# CT.net
KiCad netlist of a schematic drawn in EasyEDA Pro
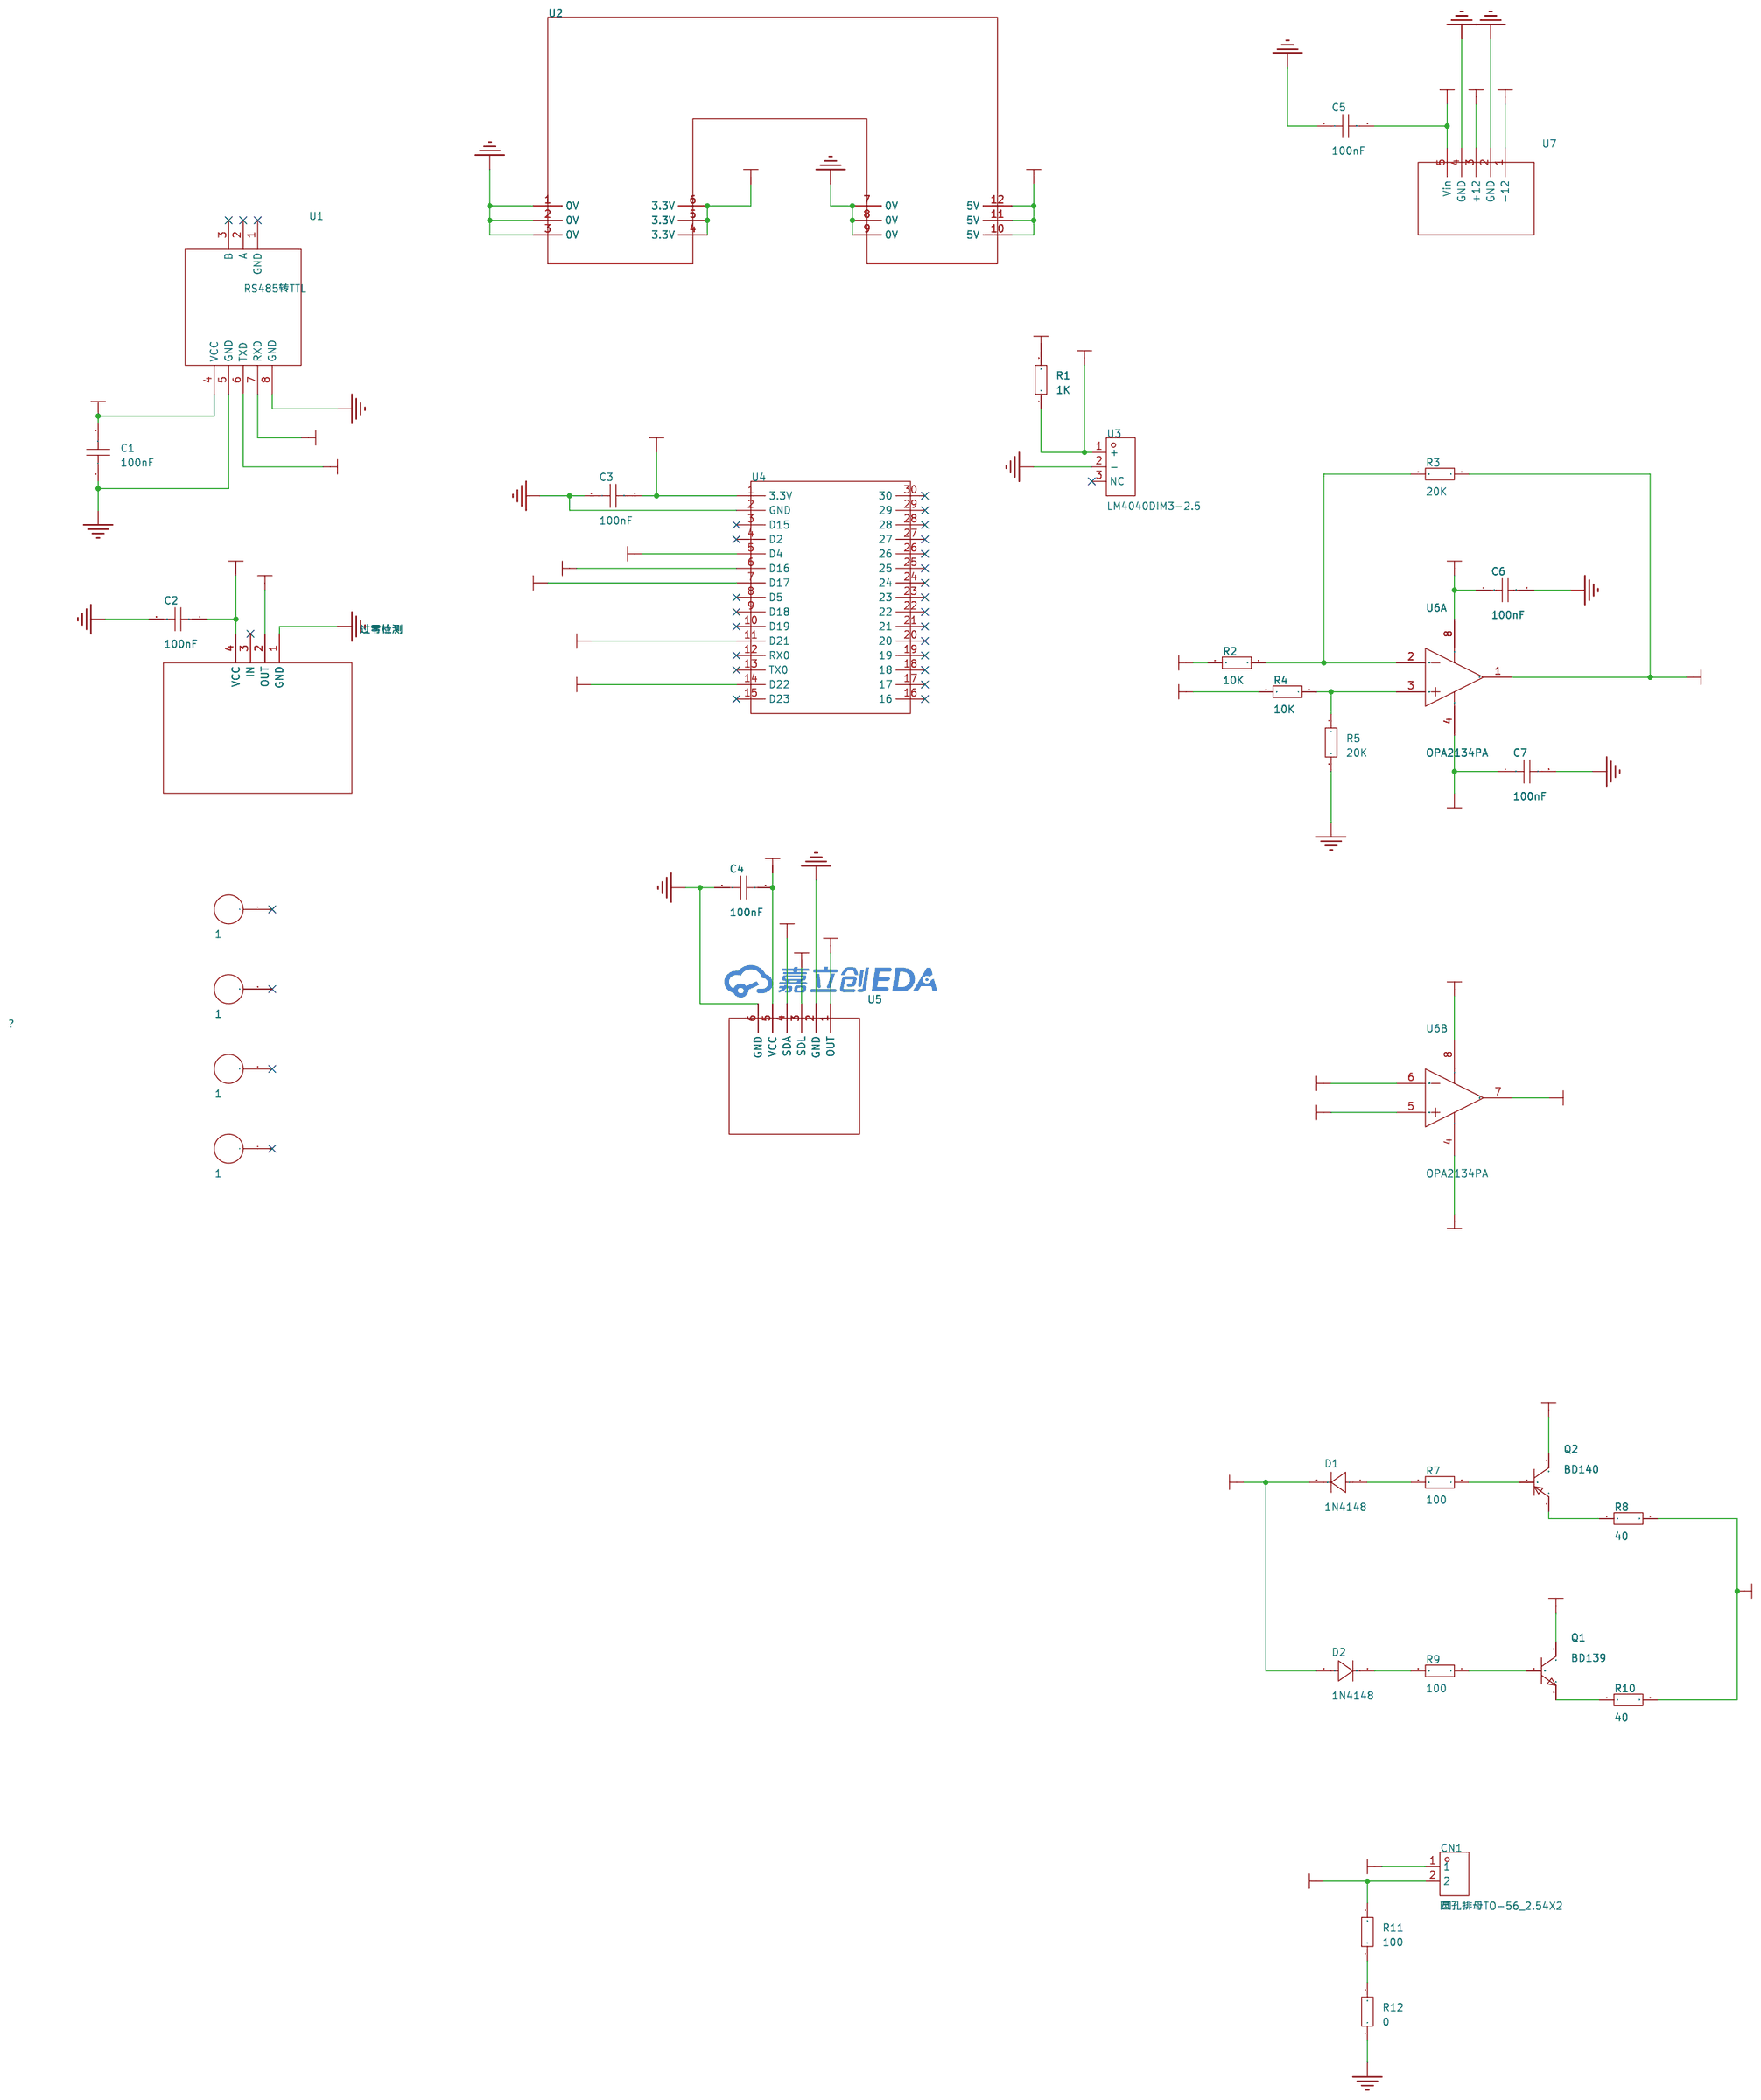
[diagram p0: schematic sheet]

(export (version "E")
  (design (tool "Eeschema 10.0.6"))
  (components
    (comp (ref "C1")
      (value "100nF")
      (footprint "easyedapro:C0805")
      (description "容值:100uF;精度:±20%;额定电压:4V;温度系数:X6S;")
      (fields
        (field (name "Manufacturer Part") "CGA0805X6S107M4R0MT")
        (field (name "Manufacturer") "HRE(芯声)")
      )
      (libsource (lib "easyedapro") (part "CGA0805X6S107M4R0MT"))
    )
    (comp (ref "C2")
      (value "100nF")
      (footprint "easyedapro:C0805")
      (description "容值:100uF;精度:±20%;额定电压:4V;温度系数:X6S;")
      (fields
        (field (name "Manufacturer Part") "CGA0805X6S107M4R0MT")
        (field (name "Manufacturer") "HRE(芯声)")
      )
      (libsource (lib "easyedapro") (part "CGA0805X6S107M4R0MT"))
    )
    (comp (ref "C3")
      (value "100nF")
      (footprint "easyedapro:C0805")
      (description "容值:100uF;精度:±20%;额定电压:4V;温度系数:X6S;")
      (fields
        (field (name "Manufacturer Part") "CGA0805X6S107M4R0MT")
        (field (name "Manufacturer") "HRE(芯声)")
      )
      (libsource (lib "easyedapro") (part "CGA0805X6S107M4R0MT"))
    )
    (comp (ref "C4")
      (value "100nF")
      (footprint "easyedapro:C0805")
      (description "容值:100uF;精度:±20%;额定电压:4V;温度系数:X6S;")
      (fields
        (field (name "Manufacturer Part") "CGA0805X6S107M4R0MT")
        (field (name "Manufacturer") "HRE(芯声)")
      )
      (libsource (lib "easyedapro") (part "CGA0805X6S107M4R0MT"))
    )
    (comp (ref "C5")
      (value "100nF")
      (footprint "easyedapro:C0805")
      (description "容值:100uF;精度:±20%;额定电压:4V;温度系数:X6S;")
      (fields
        (field (name "Manufacturer Part") "CGA0805X6S107M4R0MT")
        (field (name "Manufacturer") "HRE(芯声)")
      )
      (libsource (lib "easyedapro") (part "CGA0805X6S107M4R0MT"))
    )
    (comp (ref "C6")
      (value "100nF")
      (footprint "easyedapro:C0805")
      (description "容值:100uF;精度:±20%;额定电压:4V;温度系数:X6S;")
      (fields
        (field (name "Manufacturer Part") "CGA0805X6S107M4R0MT")
        (field (name "Manufacturer") "HRE(芯声)")
      )
      (libsource (lib "easyedapro") (part "CGA0805X6S107M4R0MT"))
    )
    (comp (ref "C7")
      (value "100nF")
      (footprint "easyedapro:C0805")
      (description "容值:100uF;精度:±20%;额定电压:4V;温度系数:X6S;")
      (fields
        (field (name "Manufacturer Part") "CGA0805X6S107M4R0MT")
        (field (name "Manufacturer") "HRE(芯声)")
      )
      (libsource (lib "easyedapro") (part "CGA0805X6S107M4R0MT"))
    )
    (comp (ref "CN1")
      (value "圆孔排母TO-56_2.54X2")
      (footprint "easyedapro:CONN-TH_TO-56_2.54-2")
      (libsource (lib "easyedapro") (part "圆孔排母TO-56_2.54X2"))
    )
    (comp (ref "D1")
      (value "1N4148")
      (footprint "easyedapro:DO-35_BD2.2-L4.0-D0.50_1N4148")
      (description "正向压降(Vf):1V@10mA;直流反向耐压(Vr):100V;整流电流:150mA;反向恢复时间(Trr):4ns;")
      (fields (field (name "Manufacturer") "LJ(朗捷)"))
      (libsource (lib "easyedapro") (part "1N4148_C18195411"))
    )
    (comp (ref "D2")
      (value "1N4148")
      (footprint "easyedapro:DO-35_BD2.2-L4.0-D0.50_1N4148")
      (description "正向压降(Vf):1V@10mA;直流反向耐压(Vr):100V;整流电流:150mA;反向恢复时间(Trr):4ns;")
      (fields (field (name "Manufacturer") "LJ(朗捷)"))
      (libsource (lib "easyedapro") (part "1N4148_C18195411"))
    )
    (comp (ref "Q1")
      (value "BD139")
      (footprint "easyedapro:TO-126_L7.5-W2.5-P2.3-B")
      (description "晶体管类型:NPN;集电极电流(Ic):1.5A;集射极击穿电压(Vceo):80V;耗散功率(Pd):12.5W;直流电流增益(hFE):63@150mA,2V;")
      (fields (field (name "Manufacturer") "ST(意法半导体)"))
      (libsource (lib "easyedapro") (part "BD139"))
    )
    (comp (ref "Q2")
      (value "BD140")
      (footprint "easyedapro:TO-126_L8.3-W3.5-P2.29-T")
      (description "晶体管类型:PNP;集电极电流(Ic):1.5A;集射极击穿电压(Vceo):80V;耗散功率(Pd):1.25W;直流电流增益(hFE):40@150mA,2V;")
      (fields (field (name "Manufacturer") "CJ(江苏长电/长晶)"))
      (libsource (lib "easyedapro") (part "BD140_C20604"))
    )
    (comp (ref "R1")
      (value "1K")
      (footprint "easyedapro:R0805")
      (description "电阻类型:厚膜电阻;阻值:1MΩ;精度:±1%;功率:125mW;最大工作电压:150V;温度系数:±100ppm/°C;")
      (fields
        (field (name "Manufacturer Part") "0805W8F1004T5E")
        (field (name "Manufacturer") "UNI-ROYAL(厚声)")
      )
      (libsource (lib "easyedapro") (part "0805W8F1004T5E"))
    )
    (comp (ref "R2")
      (value "10K")
      (footprint "easyedapro:R0805")
      (description "电阻类型:厚膜电阻;阻值:1MΩ;精度:±1%;功率:125mW;最大工作电压:150V;温度系数:±100ppm/°C;")
      (fields
        (field (name "Manufacturer Part") "0805W8F1004T5E")
        (field (name "Manufacturer") "UNI-ROYAL(厚声)")
      )
      (libsource (lib "easyedapro") (part "0805W8F1004T5E"))
    )
    (comp (ref "R3")
      (value "20K")
      (footprint "easyedapro:R0805")
      (description "电阻类型:厚膜电阻;阻值:1MΩ;精度:±1%;功率:125mW;最大工作电压:150V;温度系数:±100ppm/°C;")
      (fields
        (field (name "Manufacturer Part") "0805W8F1004T5E")
        (field (name "Manufacturer") "UNI-ROYAL(厚声)")
      )
      (libsource (lib "easyedapro") (part "0805W8F1004T5E"))
    )
    (comp (ref "R4")
      (value "10K")
      (footprint "easyedapro:R0805")
      (description "电阻类型:厚膜电阻;阻值:1MΩ;精度:±1%;功率:125mW;最大工作电压:150V;温度系数:±100ppm/°C;")
      (fields
        (field (name "Manufacturer Part") "0805W8F1004T5E")
        (field (name "Manufacturer") "UNI-ROYAL(厚声)")
      )
      (libsource (lib "easyedapro") (part "0805W8F1004T5E"))
    )
    (comp (ref "R5")
      (value "20K")
      (footprint "easyedapro:R0805")
      (description "电阻类型:厚膜电阻;阻值:1MΩ;精度:±1%;功率:125mW;最大工作电压:150V;温度系数:±100ppm/°C;")
      (fields
        (field (name "Manufacturer Part") "0805W8F1004T5E")
        (field (name "Manufacturer") "UNI-ROYAL(厚声)")
      )
      (libsource (lib "easyedapro") (part "0805W8F1004T5E"))
    )
    (comp (ref "R7")
      (value "100")
      (footprint "easyedapro:R0805")
      (description "电阻类型:厚膜电阻;阻值:1MΩ;精度:±1%;功率:125mW;最大工作电压:150V;温度系数:±100ppm/°C;")
      (fields
        (field (name "Manufacturer Part") "0805W8F1004T5E")
        (field (name "Manufacturer") "UNI-ROYAL(厚声)")
      )
      (libsource (lib "easyedapro") (part "0805W8F1004T5E"))
    )
    (comp (ref "R8")
      (value "40")
      (footprint "easyedapro:R0805")
      (description "电阻类型:厚膜电阻;阻值:1MΩ;精度:±1%;功率:125mW;最大工作电压:150V;温度系数:±100ppm/°C;")
      (fields
        (field (name "Manufacturer Part") "0805W8F1004T5E")
        (field (name "Manufacturer") "UNI-ROYAL(厚声)")
      )
      (libsource (lib "easyedapro") (part "0805W8F1004T5E"))
    )
    (comp (ref "R9")
      (value "100")
      (footprint "easyedapro:R0805")
      (description "电阻类型:厚膜电阻;阻值:1MΩ;精度:±1%;功率:125mW;最大工作电压:150V;温度系数:±100ppm/°C;")
      (fields
        (field (name "Manufacturer Part") "0805W8F1004T5E")
        (field (name "Manufacturer") "UNI-ROYAL(厚声)")
      )
      (libsource (lib "easyedapro") (part "0805W8F1004T5E"))
    )
    (comp (ref "R10")
      (value "40")
      (footprint "easyedapro:R0805")
      (description "电阻类型:厚膜电阻;阻值:1MΩ;精度:±1%;功率:125mW;最大工作电压:150V;温度系数:±100ppm/°C;")
      (fields
        (field (name "Manufacturer Part") "0805W8F1004T5E")
        (field (name "Manufacturer") "UNI-ROYAL(厚声)")
      )
      (libsource (lib "easyedapro") (part "0805W8F1004T5E"))
    )
    (comp (ref "R11")
      (value "100")
      (footprint "easyedapro:R0805")
      (description "电阻类型:厚膜电阻;阻值:1MΩ;精度:±1%;功率:125mW;最大工作电压:150V;温度系数:±100ppm/°C;")
      (fields
        (field (name "Manufacturer Part") "0805W8F1004T5E")
        (field (name "Manufacturer") "UNI-ROYAL(厚声)")
      )
      (libsource (lib "easyedapro") (part "0805W8F1004T5E"))
    )
    (comp (ref "R12")
      (value "0")
      (footprint "easyedapro:R0805")
      (description "电阻类型:厚膜电阻;阻值:1MΩ;精度:±1%;功率:125mW;最大工作电压:150V;温度系数:±100ppm/°C;")
      (fields
        (field (name "Manufacturer Part") "0805W8F1004T5E")
        (field (name "Manufacturer") "UNI-ROYAL(厚声)")
      )
      (libsource (lib "easyedapro") (part "0805W8F1004T5E"))
    )
    (comp (ref "U1")
      (value "RS485转TTL")
      (footprint "easyedapro:RS485转TTL")
      (libsource (lib "easyedapro") (part "元件"))
    )
    (comp (ref "U2")
      (value "~")
      (footprint "easyedapro:9V1A供电")
      (libsource (lib "easyedapro") (part "9V1A供电"))
    )
    (comp (ref "U3")
      (value "LM4040DIM3-2.5")
      (footprint "easyedapro:SOT-23-3_L2.9-W1.3-P1.90-LS2.4-BR")
      (description "输出类型:固定;输出电压:2.5V;输出电流:15mA;精度:±1%;")
      (fields (field (name "Manufacturer") "TI(德州仪器)"))
      (libsource (lib "easyedapro") (part "LM4040DIM3-2.5_C3717666"))
    )
    (comp (ref "U4") (value "~") (footprint "easyedapro:ESP32") (libsource (lib "easyedapro") (part "ESP32")))
    (comp (ref "U5")
      (value "~")
      (footprint "easyedapro:mcp4725")
      (libsource (lib "easyedapro") (part "mcp4725"))
    )
    (comp (ref "U6")
      (value "OPA2134PA")
      (footprint "easyedapro:DIP-8_L9.6-W6.4-P2.54-LS7.6-BL-1")
      (description "功放类型:-;扬声器通道数:双声道;输出功率:-;")
      (fields (field (name "Manufacturer") "TI(德州仪器)"))
      (libsource (lib "easyedapro") (part "OPA2134PA"))
    )
    (comp (ref "U7")
      (value "~")
      (footprint "easyedapro:12/-12")
      (libsource (lib "easyedapro") (part "12/-12"))
    )
    (comp (ref "V-PB2")
      (value "1")
      (footprint "easyedapro:SMD_BD4.2-L4.7-W4.7-D3.0")
      (description "M3*5+6")
      (fields (field (name "Manufacturer") "国产"))
      (libsource (lib "easyedapro") (part "铜柱M3*5+6"))
    )
    (comp (ref "V-PB3")
      (value "1")
      (footprint "easyedapro:SMD_BD4.2-L4.7-W4.7-D3.0")
      (description "M3*5+6")
      (fields (field (name "Manufacturer") "国产"))
      (libsource (lib "easyedapro") (part "铜柱M3*5+6"))
    )
    (comp (ref "V-PB4")
      (value "1")
      (footprint "easyedapro:SMD_BD4.2-L4.7-W4.7-D3.0")
      (description "M3*5+6")
      (fields (field (name "Manufacturer") "国产"))
      (libsource (lib "easyedapro") (part "铜柱M3*5+6"))
    )
    (comp (ref "V-PB5")
      (value "1")
      (footprint "easyedapro:SMD_BD4.2-L4.7-W4.7-D3.0")
      (description "M3*5+6")
      (fields (field (name "Manufacturer") "国产"))
      (libsource (lib "easyedapro") (part "铜柱M3*5+6"))
    )
    (comp (ref "过零检测") (value "~") (footprint "easyedapro:过零检测") (libsource (lib "easyedapro") (part "过零检测")))
  )
  (nets
    (net (code "1") (name "+12V") (class "Default")
      (node (ref "C6") (pin "1") (pinfunction "1_1") (pintype "unspecified"))
      (node (ref "Q1") (pin "2") (pinfunction "C_2") (pintype "unspecified"))
      (node (ref "U6") (pin "8") (pinfunction "V+_8") (pintype "unspecified"))
      (node (ref "U7") (pin "3") (pinfunction "+12_3") (pintype "input"))
    )
    (net (code "2") (name "-12V") (class "Default")
      (node (ref "C7") (pin "1") (pinfunction "1_1") (pintype "unspecified"))
      (node (ref "Q2") (pin "2") (pinfunction "C_2") (pintype "input"))
      (node (ref "U6") (pin "4") (pinfunction "V-_4") (pintype "unspecified"))
      (node (ref "U7") (pin "1") (pinfunction "-12_1") (pintype "input"))
    )
    (net (code "3") (name "3.3V") (class "Default")
      (node (ref "C1") (pin "2") (pinfunction "2_2") (pintype "unspecified"))
      (node (ref "C2") (pin "1") (pinfunction "1_1") (pintype "unspecified"))
      (node (ref "C3") (pin "2") (pinfunction "2_2") (pintype "unspecified"))
      (node (ref "U1") (pin "4") (pinfunction "VCC_4") (pintype "input"))
      (node (ref "U2") (pin "4") (pinfunction "3.3V_4") (pintype "input"))
      (node (ref "U2") (pin "5") (pinfunction "3.3V_5") (pintype "input"))
      (node (ref "U2") (pin "6") (pinfunction "3.3V_6") (pintype "input"))
      (node (ref "U4") (pin "1") (pinfunction "3.3V_1") (pintype "input"))
      (node (ref "过零检测") (pin "4") (pinfunction "VCC_4") (pintype "input"))
    )
    (net (code "4") (name "5V") (class "Default")
      (node (ref "C4") (pin "2") (pinfunction "2_2") (pintype "unspecified"))
      (node (ref "C5") (pin "2") (pinfunction "2_2") (pintype "unspecified"))
      (node (ref "R1") (pin "2") (pinfunction "2_2") (pintype "input"))
      (node (ref "U2") (pin "10") (pinfunction "5V_10") (pintype "input"))
      (node (ref "U2") (pin "11") (pinfunction "5V_11") (pintype "input"))
      (node (ref "U2") (pin "12") (pinfunction "5V_12") (pintype "input"))
      (node (ref "U5") (pin "5") (pinfunction "VCC_5") (pintype "input"))
      (node (ref "U7") (pin "5") (pinfunction "Vin_5") (pintype "input"))
    )
    (net (code "5") (name "CT+") (class "Default")
      (node (ref "CN1") (pin "1") (pinfunction "1_1") (pintype "unspecified"))
      (node (ref "R10") (pin "2") (pinfunction "2_2") (pintype "input"))
      (node (ref "R8") (pin "2") (pinfunction "2_2") (pintype "input"))
    )
    (net (code "6") (name "CT-") (class "Default")
      (node (ref "CN1") (pin "2") (pinfunction "2_2") (pintype "unspecified"))
      (node (ref "R11") (pin "2") (pinfunction "2_2") (pintype "input"))
      (node (ref "U6") (pin "6") (pinfunction "-IN_B_6") (pintype "unspecified"))
    )
    (net (code "7") (name "GND") (class "Default")
      (node (ref "C1") (pin "1") (pinfunction "1_1") (pintype "unspecified"))
      (node (ref "C2") (pin "2") (pinfunction "2_2") (pintype "unspecified"))
      (node (ref "C3") (pin "1") (pinfunction "1_1") (pintype "unspecified"))
      (node (ref "C4") (pin "1") (pinfunction "1_1") (pintype "unspecified"))
      (node (ref "C5") (pin "1") (pinfunction "1_1") (pintype "unspecified"))
      (node (ref "C6") (pin "2") (pinfunction "2_2") (pintype "unspecified"))
      (node (ref "C7") (pin "2") (pinfunction "2_2") (pintype "unspecified"))
      (node (ref "R12") (pin "1") (pinfunction "1_1") (pintype "input"))
      (node (ref "R5") (pin "2") (pinfunction "2_2") (pintype "input"))
      (node (ref "U1") (pin "5") (pinfunction "GND_5") (pintype "input"))
      (node (ref "U1") (pin "8") (pinfunction "GND_8") (pintype "input"))
      (node (ref "U2") (pin "1") (pinfunction "0V_1") (pintype "input"))
      (node (ref "U2") (pin "2") (pinfunction "0V_2") (pintype "input"))
      (node (ref "U2") (pin "3") (pinfunction "0V_3") (pintype "input"))
      (node (ref "U2") (pin "7") (pinfunction "0V_7") (pintype "input"))
      (node (ref "U2") (pin "8") (pinfunction "0V_8") (pintype "input"))
      (node (ref "U2") (pin "9") (pinfunction "0V_9") (pintype "input"))
      (node (ref "U3") (pin "2") (pinfunction "-_2") (pintype "unspecified"))
      (node (ref "U4") (pin "2") (pinfunction "GND_2") (pintype "input"))
      (node (ref "U5") (pin "2") (pinfunction "GND_2") (pintype "input"))
      (node (ref "U5") (pin "6") (pinfunction "GND_6") (pintype "input"))
      (node (ref "U7") (pin "2") (pinfunction "GND_2") (pintype "input"))
      (node (ref "U7") (pin "4") (pinfunction "GND_4") (pintype "input"))
      (node (ref "过零检测") (pin "1") (pinfunction "GND_1") (pintype "input"))
    )
    (net (code "8") (name "LM4040_2.5") (class "Default")
      (node (ref "R1") (pin "1") (pinfunction "1_1") (pintype "input"))
      (node (ref "R2") (pin "2") (pinfunction "2_2") (pintype "input"))
      (node (ref "U3") (pin "1") (pinfunction "+_1") (pintype "unspecified"))
    )
    (net (code "9") (name "Net-(D1-A)") (class "Default")
      (node (ref "D1") (pin "1") (pinfunction "A_1") (pintype "unspecified"))
      (node (ref "R7") (pin "2") (pinfunction "2_2") (pintype "input"))
    )
    (net (code "10") (name "Net-(D2-C)") (class "Default")
      (node (ref "D2") (pin "2") (pinfunction "C_2") (pintype "unspecified"))
      (node (ref "R9") (pin "2") (pinfunction "2_2") (pintype "input"))
    )
    (net (code "11") (name "Net-(Q1-B)") (class "Default")
      (node (ref "Q1") (pin "1") (pinfunction "B_1") (pintype "unspecified"))
      (node (ref "R9") (pin "1") (pinfunction "1_1") (pintype "input"))
    )
    (net (code "12") (name "Net-(Q1-E)") (class "Default")
      (node (ref "Q1") (pin "3") (pinfunction "E_3") (pintype "unspecified"))
      (node (ref "R10") (pin "1") (pinfunction "1_1") (pintype "input"))
    )
    (net (code "13") (name "Net-(Q2-B)") (class "Default")
      (node (ref "Q2") (pin "3") (pinfunction "B_3") (pintype "input"))
      (node (ref "R7") (pin "1") (pinfunction "1_1") (pintype "input"))
    )
    (net (code "14") (name "Net-(Q2-E)") (class "Default")
      (node (ref "Q2") (pin "1") (pinfunction "E_1") (pintype "input"))
      (node (ref "R8") (pin "1") (pinfunction "1_1") (pintype "input"))
    )
    (net (code "15") (name "Net-(R11-Pad1)") (class "Default")
      (node (ref "R11") (pin "1") (pinfunction "1_1") (pintype "input"))
      (node (ref "R12") (pin "2") (pinfunction "2_2") (pintype "input"))
    )
    (net (code "16") (name "Net-(U6A-+IN_A)") (class "Default")
      (node (ref "R4") (pin "1") (pinfunction "1_1") (pintype "input"))
      (node (ref "R5") (pin "1") (pinfunction "1_1") (pintype "input"))
      (node (ref "U6") (pin "3") (pinfunction "+IN_A_3") (pintype "unspecified"))
    )
    (net (code "17") (name "Net-(U6A--IN_A)") (class "Default")
      (node (ref "R2") (pin "1") (pinfunction "1_1") (pintype "input"))
      (node (ref "R3") (pin "2") (pinfunction "2_2") (pintype "input"))
      (node (ref "U6") (pin "2") (pinfunction "-IN_A_2") (pintype "unspecified"))
    )
    (net (code "18") (name "OUT_0") (class "Default")
      (node (ref "U4") (pin "5") (pinfunction "D4_5") (pintype "input"))
      (node (ref "过零检测") (pin "2") (pinfunction "OUT_2") (pintype "input"))
    )
    (net (code "19") (name "OUT_MCP4725") (class "Default")
      (node (ref "R4") (pin "2") (pinfunction "2_2") (pintype "input"))
      (node (ref "U5") (pin "1") (pinfunction "OUT_1") (pintype "input"))
    )
    (net (code "20") (name "RX") (class "Default")
      (node (ref "U1") (pin "7") (pinfunction "RXD_7") (pintype "input"))
      (node (ref "U4") (pin "6") (pinfunction "D16_6") (pintype "input"))
    )
    (net (code "21") (name "SDA") (class "Default")
      (node (ref "U4") (pin "11") (pinfunction "D21_11") (pintype "input"))
      (node (ref "U5") (pin "4") (pinfunction "SDA_4") (pintype "input"))
    )
    (net (code "22") (name "SDL") (class "Default")
      (node (ref "U4") (pin "14") (pinfunction "D22_14") (pintype "input"))
      (node (ref "U5") (pin "3") (pinfunction "SDL_3") (pintype "input"))
    )
    (net (code "23") (name "TX") (class "Default")
      (node (ref "U1") (pin "6") (pinfunction "TXD_6") (pintype "input"))
      (node (ref "U4") (pin "7") (pinfunction "D17_7") (pintype "input"))
    )
    (net (code "24") (name "VOUT1") (class "Default")
      (node (ref "R3") (pin "1") (pinfunction "1_1") (pintype "input"))
      (node (ref "U6") (pin "1") (pinfunction "OUT_A_1") (pintype "output"))
      (node (ref "U6") (pin "5") (pinfunction "+IN_B_5") (pintype "unspecified"))
    )
    (net (code "25") (name "VOUT2") (class "Default")
      (node (ref "D1") (pin "2") (pinfunction "C_2") (pintype "unspecified"))
      (node (ref "D2") (pin "1") (pinfunction "A_1") (pintype "unspecified"))
      (node (ref "U6") (pin "7") (pinfunction "OUT_B_7") (pintype "output"))
    )
    (net (code "26") (name "unconnected-(U1-A-Pad2)") (class "Default")
      (node (ref "U1") (pin "2") (pinfunction "A_2") (pintype "input+no_connect"))
    )
    (net (code "27") (name "unconnected-(U1-B-Pad3)") (class "Default")
      (node (ref "U1") (pin "3") (pinfunction "B_3") (pintype "input+no_connect"))
    )
    (net (code "28") (name "unconnected-(U1-GND-Pad1)") (class "Default")
      (node (ref "U1") (pin "1") (pinfunction "GND_1") (pintype "input+no_connect"))
    )
    (net (code "29") (name "unconnected-(U3-NC-Pad3)") (class "Default")
      (node (ref "U3") (pin "3") (pinfunction "NC_3") (pintype "unspecified+no_connect"))
    )
    (net (code "30") (name "unconnected-(U4-D2-Pad4)") (class "Default")
      (node (ref "U4") (pin "4") (pinfunction "D2_4") (pintype "input+no_connect"))
    )
    (net (code "31") (name "unconnected-(U4-D5-Pad8)") (class "Default")
      (node (ref "U4") (pin "8") (pinfunction "D5_8") (pintype "input+no_connect"))
    )
    (net (code "32") (name "unconnected-(U4-D15-Pad3)") (class "Default")
      (node (ref "U4") (pin "3") (pinfunction "D15_3") (pintype "input+no_connect"))
    )
    (net (code "33") (name "unconnected-(U4-D18-Pad9)") (class "Default")
      (node (ref "U4") (pin "9") (pinfunction "D18_9") (pintype "input+no_connect"))
    )
    (net (code "34") (name "unconnected-(U4-D19-Pad10)") (class "Default")
      (node (ref "U4") (pin "10") (pinfunction "D19_10") (pintype "input+no_connect"))
    )
    (net (code "35") (name "unconnected-(U4-D23-Pad15)") (class "Default")
      (node (ref "U4") (pin "15") (pinfunction "D23_15") (pintype "input+no_connect"))
    )
    (net (code "36") (name "unconnected-(U4-Pad16)") (class "Default")
      (node (ref "U4") (pin "16") (pinfunction "16_16") (pintype "input+no_connect"))
    )
    (net (code "37") (name "unconnected-(U4-Pad17)") (class "Default")
      (node (ref "U4") (pin "17") (pinfunction "17_17") (pintype "input+no_connect"))
    )
    (net (code "38") (name "unconnected-(U4-Pad18)") (class "Default")
      (node (ref "U4") (pin "18") (pinfunction "18_18") (pintype "input+no_connect"))
    )
    (net (code "39") (name "unconnected-(U4-Pad19)") (class "Default")
      (node (ref "U4") (pin "19") (pinfunction "19_19") (pintype "input+no_connect"))
    )
    (net (code "40") (name "unconnected-(U4-Pad20)") (class "Default")
      (node (ref "U4") (pin "20") (pinfunction "20_20") (pintype "input+no_connect"))
    )
    (net (code "41") (name "unconnected-(U4-Pad21)") (class "Default")
      (node (ref "U4") (pin "21") (pinfunction "21_21") (pintype "input+no_connect"))
    )
    (net (code "42") (name "unconnected-(U4-Pad22)") (class "Default")
      (node (ref "U4") (pin "22") (pinfunction "22_22") (pintype "input+no_connect"))
    )
    (net (code "43") (name "unconnected-(U4-Pad23)") (class "Default")
      (node (ref "U4") (pin "23") (pinfunction "23_23") (pintype "input+no_connect"))
    )
    (net (code "44") (name "unconnected-(U4-Pad24)") (class "Default")
      (node (ref "U4") (pin "24") (pinfunction "24_24") (pintype "input+no_connect"))
    )
    (net (code "45") (name "unconnected-(U4-Pad25)") (class "Default")
      (node (ref "U4") (pin "25") (pinfunction "25_25") (pintype "input+no_connect"))
    )
    (net (code "46") (name "unconnected-(U4-Pad26)") (class "Default")
      (node (ref "U4") (pin "26") (pinfunction "26_26") (pintype "input+no_connect"))
    )
    (net (code "47") (name "unconnected-(U4-Pad27)") (class "Default")
      (node (ref "U4") (pin "27") (pinfunction "27_27") (pintype "input+no_connect"))
    )
    (net (code "48") (name "unconnected-(U4-Pad28)") (class "Default")
      (node (ref "U4") (pin "28") (pinfunction "28_28") (pintype "input+no_connect"))
    )
    (net (code "49") (name "unconnected-(U4-Pad29)") (class "Default")
      (node (ref "U4") (pin "29") (pinfunction "29_29") (pintype "input+no_connect"))
    )
    (net (code "50") (name "unconnected-(U4-Pad30)") (class "Default")
      (node (ref "U4") (pin "30") (pinfunction "30_30") (pintype "input+no_connect"))
    )
    (net (code "51") (name "unconnected-(U4-RX0-Pad12)") (class "Default")
      (node (ref "U4") (pin "12") (pinfunction "RX0_12") (pintype "input+no_connect"))
    )
    (net (code "52") (name "unconnected-(U4-TX0-Pad13)") (class "Default")
      (node (ref "U4") (pin "13") (pinfunction "TX0_13") (pintype "input+no_connect"))
    )
    (net (code "53") (name "unconnected-(V-PB2-Pad1)") (class "Default")
      (node (ref "V-PB2") (pin "1") (pinfunction "1_1") (pintype "unspecified+no_connect"))
    )
    (net (code "54") (name "unconnected-(V-PB3-Pad1)") (class "Default")
      (node (ref "V-PB3") (pin "1") (pinfunction "1_1") (pintype "unspecified+no_connect"))
    )
    (net (code "55") (name "unconnected-(V-PB4-Pad1)") (class "Default")
      (node (ref "V-PB4") (pin "1") (pinfunction "1_1") (pintype "unspecified+no_connect"))
    )
    (net (code "56") (name "unconnected-(V-PB5-Pad1)") (class "Default")
      (node (ref "V-PB5") (pin "1") (pinfunction "1_1") (pintype "unspecified+no_connect"))
    )
    (net (code "57") (name "unconnected-(过零检测-IN-Pad3)") (class "Default")
      (node (ref "过零检测") (pin "3") (pinfunction "IN_3") (pintype "input+no_connect"))
    )
  )
)
